# TBController_Teensy_3_2.net
KiCad netlist of a schematic drawn in EAGLE
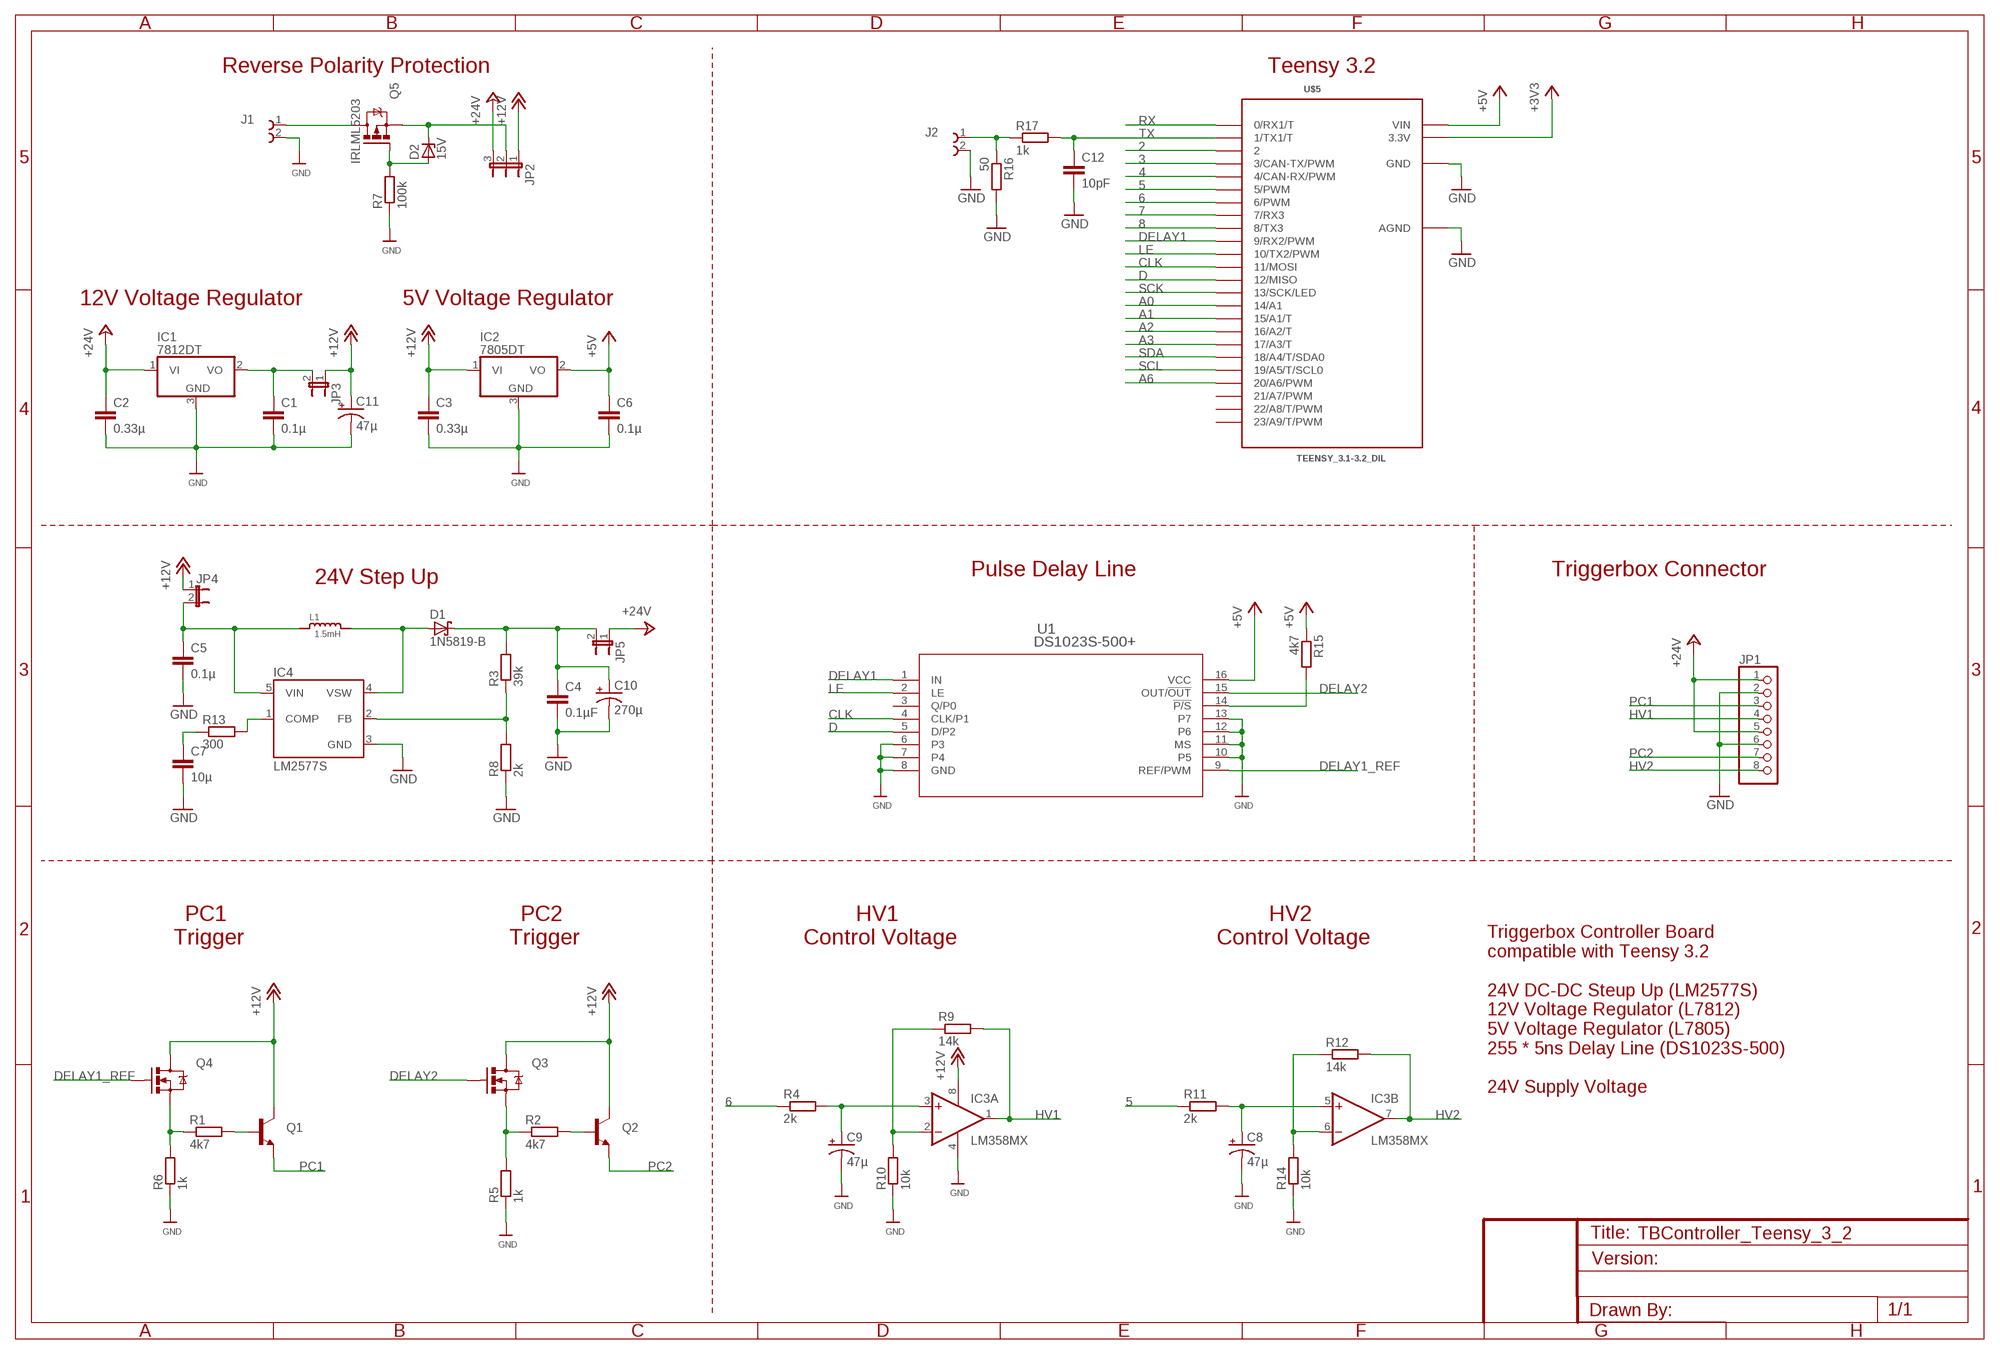
[diagram p0: schematic, sheet 1]

(export (version "E")
  (design (tool "Eeschema 10.0.6"))
  (components
    (comp (ref "C1")
      (value "0.1µ")
      (footprint "eagle-import:C0805K")
      (libsource (lib "eagle-import") (part "C-EUC0805K"))
    )
    (comp (ref "C2")
      (value "0.33µ")
      (footprint "eagle-import:C0805K")
      (libsource (lib "eagle-import") (part "C-EUC0805K"))
    )
    (comp (ref "C3")
      (value "0.33µ")
      (footprint "eagle-import:C0805K")
      (libsource (lib "eagle-import") (part "C-EUC0805K"))
    )
    (comp (ref "C4")
      (value "0.1µF")
      (footprint "eagle-import:C0805K")
      (libsource (lib "eagle-import") (part "C-EUC0805K"))
    )
    (comp (ref "C5")
      (value "0.1µ")
      (footprint "eagle-import:C0805K")
      (libsource (lib "eagle-import") (part "C-EUC0805K"))
    )
    (comp (ref "C6")
      (value "0.1µ")
      (footprint "eagle-import:C0805K")
      (libsource (lib "eagle-import") (part "C-EUC0805K"))
    )
    (comp (ref "C7")
      (value "10µ")
      (footprint "eagle-import:C0805K")
      (libsource (lib "eagle-import") (part "C-EUC0805K"))
    )
    (comp (ref "C8")
      (value "47µ")
      (footprint "eagle-import:CPOL-RADIAL-100UF-25V")
      (libsource (lib "eagle-import") (part "CAP_POLPTH1"))
    )
    (comp (ref "C9")
      (value "47µ")
      (footprint "eagle-import:CPOL-RADIAL-100UF-25V")
      (libsource (lib "eagle-import") (part "CAP_POLPTH1"))
    )
    (comp (ref "C10")
      (value "270µ")
      (footprint "eagle-import:CPOL-RADIAL-100UF-25V")
      (libsource (lib "eagle-import") (part "CAP_POLPTH1"))
    )
    (comp (ref "C11")
      (value "47µ")
      (footprint "eagle-import:CPOL-RADIAL-100UF-25V")
      (libsource (lib "eagle-import") (part "CAP_POLPTH1"))
    )
    (comp (ref "C12")
      (value "10pF")
      (footprint "eagle-import:C0805K")
      (libsource (lib "eagle-import") (part "C-EUC0805K"))
    )
    (comp (ref "D1")
      (value "1N5819-B")
      (footprint "eagle-import:DO41-7.6")
      (libsource (lib "eagle-import") (part "1N5819-B"))
    )
    (comp (ref "D2")
      (value "15V")
      (footprint "eagle-import:SOT23")
      (libsource (lib "eagle-import") (part "ZENER-DIODESOT23"))
    )
    (comp (ref "IC1")
      (value "7812DT")
      (footprint "eagle-import:TO252")
      (libsource (lib "eagle-import") (part "78DT12"))
    )
    (comp (ref "IC2")
      (value "7805DT")
      (footprint "eagle-import:TO252")
      (libsource (lib "eagle-import") (part "78DT05"))
    )
    (comp (ref "IC3")
      (value "LM358MX")
      (footprint "eagle-import:SO08")
      (libsource (lib "eagle-import") (part "LM358MX"))
    )
    (comp (ref "IC4")
      (value "LM2577S")
      (footprint "eagle-import:TO263-5")
      (libsource (lib "eagle-import") (part "LM2577S"))
    )
    (comp (ref "J1")
      (value "691103110002")
      (footprint "eagle-import:691103110002")
      (libsource (lib "eagle-import") (part "691103110002"))
    )
    (comp (ref "J2")
      (value "691103110002")
      (footprint "eagle-import:691103110002")
      (libsource (lib "eagle-import") (part "691103110002"))
    )
    (comp (ref "JP1")
      (value "PINHD-1X8")
      (footprint "eagle-import:1X08")
      (libsource (lib "eagle-import") (part "PINHD-1X8"))
    )
    (comp (ref "JP2")
      (value "JP2E")
      (footprint "eagle-import:JP2")
      (libsource (lib "eagle-import") (part "JP2E"))
    )
    (comp (ref "JP3")
      (value "JUMPER-2PTH_LOCK")
      (footprint "eagle-import:1X02_LOCK")
      (libsource (lib "eagle-import") (part "JUMPER-2PTH_LOCK"))
    )
    (comp (ref "JP4")
      (value "JUMPER-2PTH_LOCK")
      (footprint "eagle-import:1X02_LOCK")
      (libsource (lib "eagle-import") (part "JUMPER-2PTH_LOCK"))
    )
    (comp (ref "JP5")
      (value "JUMPER-2PTH_LOCK")
      (footprint "eagle-import:1X02_LOCK")
      (libsource (lib "eagle-import") (part "JUMPER-2PTH_LOCK"))
    )
    (comp (ref "L1")
      (value "1.5mH")
      (footprint "eagle-import:WUERTH_WE_PD")
      (libsource (lib "eagle-import") (part "SPULE"))
    )
    (comp (ref "Q1")
      (value "TRANSISTOR_NPNSOT23")
      (footprint "eagle-import:SOT23")
      (libsource (lib "eagle-import") (part "TRANSISTOR_NPNSOT23"))
    )
    (comp (ref "Q2")
      (value "TRANSISTOR_NPNSOT23")
      (footprint "eagle-import:SOT23")
      (libsource (lib "eagle-import") (part "TRANSISTOR_NPNSOT23"))
    )
    (comp (ref "Q3")
      (value "MOSFET-NCHANNELSMD")
      (footprint "eagle-import:SOT23-3")
      (libsource (lib "eagle-import") (part "MOSFET-NCHANNELSMD"))
    )
    (comp (ref "Q4")
      (value "MOSFET-NCHANNELSMD")
      (footprint "eagle-import:SOT23-3")
      (libsource (lib "eagle-import") (part "MOSFET-NCHANNELSMD"))
    )
    (comp (ref "Q5")
      (value "IRLML5203")
      (footprint "eagle-import:MICRO3")
      (libsource (lib "eagle-import") (part "IRLML5203"))
    )
    (comp (ref "R1")
      (value "4k7")
      (footprint "eagle-import:R0805")
      (libsource (lib "eagle-import") (part "R-EU_R0805"))
    )
    (comp (ref "R2")
      (value "4k7")
      (footprint "eagle-import:R0805")
      (libsource (lib "eagle-import") (part "R-EU_R0805"))
    )
    (comp (ref "R3")
      (value "39k")
      (footprint "eagle-import:R0805")
      (libsource (lib "eagle-import") (part "R-EU_R0805"))
    )
    (comp (ref "R4")
      (value "2k")
      (footprint "eagle-import:R0805")
      (libsource (lib "eagle-import") (part "R-EU_R0805"))
    )
    (comp (ref "R5")
      (value "1k")
      (footprint "eagle-import:R0805")
      (libsource (lib "eagle-import") (part "R-EU_R0805"))
    )
    (comp (ref "R6")
      (value "1k")
      (footprint "eagle-import:R0805")
      (libsource (lib "eagle-import") (part "R-EU_R0805"))
    )
    (comp (ref "R7")
      (value "100k")
      (footprint "eagle-import:R0805")
      (libsource (lib "eagle-import") (part "R-EU_R0805"))
    )
    (comp (ref "R8")
      (value "2k")
      (footprint "eagle-import:R0805")
      (libsource (lib "eagle-import") (part "R-EU_R0805"))
    )
    (comp (ref "R9")
      (value "14k")
      (footprint "eagle-import:R0805")
      (libsource (lib "eagle-import") (part "R-EU_R0805"))
    )
    (comp (ref "R10")
      (value "10k")
      (footprint "eagle-import:R0805")
      (libsource (lib "eagle-import") (part "R-EU_R0805"))
    )
    (comp (ref "R11")
      (value "2k")
      (footprint "eagle-import:R0805")
      (libsource (lib "eagle-import") (part "R-EU_R0805"))
    )
    (comp (ref "R12")
      (value "14k")
      (footprint "eagle-import:R0805")
      (libsource (lib "eagle-import") (part "R-EU_R0805"))
    )
    (comp (ref "R13")
      (value "300")
      (footprint "eagle-import:R0805")
      (libsource (lib "eagle-import") (part "R-EU_R0805"))
    )
    (comp (ref "R14")
      (value "10k")
      (footprint "eagle-import:R0805")
      (libsource (lib "eagle-import") (part "R-EU_R0805"))
    )
    (comp (ref "R15")
      (value "4k7")
      (footprint "eagle-import:R0805")
      (libsource (lib "eagle-import") (part "R-EU_R0805"))
    )
    (comp (ref "R16")
      (value "50")
      (footprint "eagle-import:R0805")
      (libsource (lib "eagle-import") (part "R-EU_R0805"))
    )
    (comp (ref "R17")
      (value "1k")
      (footprint "eagle-import:R0805")
      (libsource (lib "eagle-import") (part "R-EU_R0805"))
    )
    (comp (ref "U$5")
      (value "TEENSY_3.1-3.2_DIL")
      (footprint "eagle-import:TEENSY_3.0-3.2&LC_DIL")
      (libsource (lib "eagle-import") (part "TEENSY_3.1-3.2_DIL"))
    )
    (comp (ref "U1")
      (value "DS1023S-500+")
      (footprint "eagle-import:21-0042B_16")
      (fields (field (name "MANUFACTURER_PART_NUMBER") "DS1023S500+"))
      (libsource (lib "eagle-import") (part "DS1023S-500+"))
    )
  )
  (nets
    (net (code "1") (name "+3V3") (class "Default")
      (node (ref "U$5") (pin "3.3V") (pinfunction "3.3V_3.3V") (pintype "power_in"))
    )
    (net (code "2") (name "+5V") (class "Default")
      (node (ref "C6") (pin "1") (pinfunction "1_1") (pintype "passive"))
      (node (ref "IC2") (pin "2") (pinfunction "VO_2") (pintype "passive"))
      (node (ref "R15") (pin "1") (pinfunction "1_1") (pintype "passive"))
      (node (ref "U$5") (pin "VIN") (pinfunction "VIN_VIN") (pintype "power_in"))
      (node (ref "U1") (pin "16") (pinfunction "VCC_16") (pintype "power_in"))
    )
    (net (code "3") (name "+12V") (class "Default")
      (node (ref "C11") (pin "1") (pinfunction "+_1") (pintype "passive"))
      (node (ref "C3") (pin "1") (pinfunction "1_1") (pintype "passive"))
      (node (ref "IC2") (pin "1") (pinfunction "VI_1") (pintype "input"))
      (node (ref "IC3") (pin "8") (pinfunction "V+_8") (pintype "power_in"))
      (node (ref "JP2") (pin "1") (pinfunction "1_1") (pintype "passive"))
      (node (ref "JP3") (pin "1") (pinfunction "1_1") (pintype "passive"))
      (node (ref "JP4") (pin "1") (pinfunction "1_1") (pintype "passive"))
      (node (ref "Q1") (pin "3") (pinfunction "C_3") (pintype "passive"))
      (node (ref "Q2") (pin "3") (pinfunction "C_3") (pintype "passive"))
      (node (ref "Q3") (pin "3") (pinfunction "D_3") (pintype "passive"))
      (node (ref "Q4") (pin "3") (pinfunction "D_3") (pintype "passive"))
    )
    (net (code "4") (name "+24V") (class "Default")
      (node (ref "C2") (pin "1") (pinfunction "1_1") (pintype "passive"))
      (node (ref "IC1") (pin "1") (pinfunction "VI_1") (pintype "input"))
      (node (ref "JP1") (pin "1") (pinfunction "1_1") (pintype "passive"))
      (node (ref "JP1") (pin "5") (pinfunction "5_5") (pintype "passive"))
      (node (ref "JP2") (pin "3") (pinfunction "3_3") (pintype "passive"))
      (node (ref "JP5") (pin "1") (pinfunction "1_1") (pintype "passive"))
    )
    (net (code "5") (name "/2") (class "Default")
      (node (ref "U$5") (pin "2") (pinfunction "2_2") (pintype "bidirectional"))
    )
    (net (code "6") (name "/3") (class "Default")
      (node (ref "U$5") (pin "3") (pinfunction "3/CAN-TX/PWM_3") (pintype "bidirectional"))
    )
    (net (code "7") (name "/4") (class "Default")
      (node (ref "U$5") (pin "4") (pinfunction "4/CAN-RX/PWM_4") (pintype "bidirectional"))
    )
    (net (code "8") (name "/5") (class "Default")
      (node (ref "R11") (pin "1") (pinfunction "1_1") (pintype "passive"))
      (node (ref "U$5") (pin "5") (pinfunction "5/PWM_5") (pintype "bidirectional"))
    )
    (net (code "9") (name "/6") (class "Default")
      (node (ref "R4") (pin "1") (pinfunction "1_1") (pintype "passive"))
      (node (ref "U$5") (pin "6") (pinfunction "6/PWM_6") (pintype "bidirectional"))
    )
    (net (code "10") (name "/7") (class "Default")
      (node (ref "U$5") (pin "7") (pinfunction "7/RX3_7") (pintype "bidirectional"))
    )
    (net (code "11") (name "/8") (class "Default")
      (node (ref "U$5") (pin "8") (pinfunction "8/TX3_8") (pintype "bidirectional"))
    )
    (net (code "12") (name "/A0") (class "Default")
      (node (ref "U$5") (pin "14/A0") (pinfunction "14/A1_14/A0") (pintype "bidirectional"))
    )
    (net (code "13") (name "/A1") (class "Default")
      (node (ref "U$5") (pin "15/A1") (pinfunction "15/A1/T_15/A1") (pintype "bidirectional"))
    )
    (net (code "14") (name "/A2") (class "Default")
      (node (ref "U$5") (pin "16/A2") (pinfunction "16/A2/T_16/A2") (pintype "bidirectional"))
    )
    (net (code "15") (name "/A3") (class "Default")
      (node (ref "U$5") (pin "17/A3") (pinfunction "17/A3/T_17/A3") (pintype "bidirectional"))
    )
    (net (code "16") (name "/A6") (class "Default")
      (node (ref "U$5") (pin "20/A6") (pinfunction "20/A6/PWM_20/A6") (pintype "bidirectional"))
    )
    (net (code "17") (name "/CLK") (class "Default")
      (node (ref "U$5") (pin "11") (pinfunction "11/MOSI_11") (pintype "bidirectional"))
      (node (ref "U1") (pin "4") (pinfunction "CLK/P1_4") (pintype "passive"))
    )
    (net (code "18") (name "/D") (class "Default")
      (node (ref "U$5") (pin "12") (pinfunction "12/MISO_12") (pintype "bidirectional"))
      (node (ref "U1") (pin "5") (pinfunction "D/P2_5") (pintype "passive"))
    )
    (net (code "19") (name "/DELAY1") (class "Default")
      (node (ref "U$5") (pin "9") (pinfunction "9/RX2/PWM_9") (pintype "bidirectional"))
      (node (ref "U1") (pin "1") (pinfunction "IN_1") (pintype "input"))
    )
    (net (code "20") (name "/DELAY1_REF") (class "Default")
      (node (ref "Q4") (pin "1") (pinfunction "G_1") (pintype "passive"))
      (node (ref "U1") (pin "9") (pinfunction "REF/PWM_9") (pintype "passive"))
    )
    (net (code "21") (name "/DELAY2") (class "Default")
      (node (ref "Q3") (pin "1") (pinfunction "G_1") (pintype "passive"))
      (node (ref "U1") (pin "15") (pinfunction "OUT/~{OUT}_15") (pintype "passive"))
    )
    (net (code "22") (name "/HV1") (class "Default")
      (node (ref "IC3") (pin "1") (pinfunction "OUT_1") (pintype "output"))
      (node (ref "JP1") (pin "4") (pinfunction "4_4") (pintype "passive"))
      (node (ref "R9") (pin "2") (pinfunction "2_2") (pintype "passive"))
    )
    (net (code "23") (name "/HV2") (class "Default")
      (node (ref "IC3") (pin "7") (pinfunction "OUT_7") (pintype "output"))
      (node (ref "JP1") (pin "8") (pinfunction "8_8") (pintype "passive"))
      (node (ref "R12") (pin "2") (pinfunction "2_2") (pintype "passive"))
    )
    (net (code "24") (name "/LE") (class "Default")
      (node (ref "U$5") (pin "10") (pinfunction "10/TX2/PWM_10") (pintype "bidirectional"))
      (node (ref "U1") (pin "2") (pinfunction "LE_2") (pintype "passive"))
    )
    (net (code "25") (name "/PC1") (class "Default")
      (node (ref "JP1") (pin "3") (pinfunction "3_3") (pintype "passive"))
      (node (ref "Q1") (pin "2") (pinfunction "E_2") (pintype "passive"))
    )
    (net (code "26") (name "/PC2") (class "Default")
      (node (ref "JP1") (pin "7") (pinfunction "7_7") (pintype "passive"))
      (node (ref "Q2") (pin "2") (pinfunction "E_2") (pintype "passive"))
    )
    (net (code "27") (name "/RX") (class "Default")
      (node (ref "U$5") (pin "0") (pinfunction "0/RX1/T_0") (pintype "bidirectional"))
    )
    (net (code "28") (name "/SCK") (class "Default")
      (node (ref "U$5") (pin "13") (pinfunction "13/SCK/LED_13") (pintype "bidirectional"))
    )
    (net (code "29") (name "/SCL") (class "Default")
      (node (ref "U$5") (pin "19/A5") (pinfunction "19/A5/T/SCL0_19/A5") (pintype "bidirectional"))
    )
    (net (code "30") (name "/SDA") (class "Default")
      (node (ref "U$5") (pin "18/A4") (pinfunction "18/A4/T/SDA0_18/A4") (pintype "bidirectional"))
    )
    (net (code "31") (name "/TX") (class "Default")
      (node (ref "J2") (pin "1") (pinfunction "1_1") (pintype "passive"))
      (node (ref "R16") (pin "1") (pinfunction "1_1") (pintype "passive"))
      (node (ref "R17") (pin "1") (pinfunction "1_1") (pintype "passive"))
    )
    (net (code "32") (name "GND") (class "Default")
      (node (ref "C1") (pin "2") (pinfunction "2_2") (pintype "passive"))
      (node (ref "C10") (pin "2") (pinfunction "-_2") (pintype "passive"))
      (node (ref "C11") (pin "2") (pinfunction "-_2") (pintype "passive"))
      (node (ref "C12") (pin "2") (pinfunction "2_2") (pintype "passive"))
      (node (ref "C2") (pin "2") (pinfunction "2_2") (pintype "passive"))
      (node (ref "C3") (pin "2") (pinfunction "2_2") (pintype "passive"))
      (node (ref "C4") (pin "2") (pinfunction "2_2") (pintype "passive"))
      (node (ref "C5") (pin "2") (pinfunction "2_2") (pintype "passive"))
      (node (ref "C6") (pin "2") (pinfunction "2_2") (pintype "passive"))
      (node (ref "C7") (pin "2") (pinfunction "2_2") (pintype "passive"))
      (node (ref "C8") (pin "2") (pinfunction "-_2") (pintype "passive"))
      (node (ref "C9") (pin "2") (pinfunction "-_2") (pintype "passive"))
      (node (ref "IC1") (pin "3") (pinfunction "GND_3") (pintype "passive"))
      (node (ref "IC2") (pin "3") (pinfunction "GND_3") (pintype "passive"))
      (node (ref "IC3") (pin "4") (pinfunction "V-_4") (pintype "power_in"))
      (node (ref "IC4") (pin "3") (pinfunction "GND_3") (pintype "power_in"))
      (node (ref "J1") (pin "2") (pinfunction "2_2") (pintype "passive"))
      (node (ref "J2") (pin "2") (pinfunction "2_2") (pintype "passive"))
      (node (ref "JP1") (pin "2") (pinfunction "2_2") (pintype "passive"))
      (node (ref "JP1") (pin "6") (pinfunction "6_6") (pintype "passive"))
      (node (ref "R10") (pin "1") (pinfunction "1_1") (pintype "passive"))
      (node (ref "R14") (pin "1") (pinfunction "1_1") (pintype "passive"))
      (node (ref "R16") (pin "2") (pinfunction "2_2") (pintype "passive"))
      (node (ref "R5") (pin "1") (pinfunction "1_1") (pintype "passive"))
      (node (ref "R6") (pin "1") (pinfunction "1_1") (pintype "passive"))
      (node (ref "R7") (pin "1") (pinfunction "1_1") (pintype "passive"))
      (node (ref "R8") (pin "1") (pinfunction "1_1") (pintype "passive"))
      (node (ref "U$5") (pin "AGND") (pinfunction "AGND_AGND") (pintype "power_in"))
      (node (ref "U$5") (pin "GND") (pinfunction "GND_GND") (pintype "power_in"))
      (node (ref "U1") (pin "10") (pinfunction "P5_10") (pintype "passive"))
      (node (ref "U1") (pin "11") (pinfunction "MS_11") (pintype "passive"))
      (node (ref "U1") (pin "12") (pinfunction "P6_12") (pintype "passive"))
      (node (ref "U1") (pin "13") (pinfunction "P7_13") (pintype "passive"))
      (node (ref "U1") (pin "6") (pinfunction "P3_6") (pintype "passive"))
      (node (ref "U1") (pin "7") (pinfunction "P4_7") (pintype "passive"))
      (node (ref "U1") (pin "8") (pinfunction "GND_8") (pintype "power_in"))
    )
    (net (code "33") (name "Net-(C7-Pad1)") (class "Default")
      (node (ref "C7") (pin "1") (pinfunction "1_1") (pintype "passive"))
      (node (ref "R13") (pin "1") (pinfunction "1_1") (pintype "passive"))
    )
    (net (code "34") (name "Net-(C8-+)") (class "Default")
      (node (ref "C8") (pin "1") (pinfunction "+_1") (pintype "passive"))
      (node (ref "IC3") (pin "5") (pinfunction "+IN_5") (pintype "input"))
      (node (ref "R11") (pin "2") (pinfunction "2_2") (pintype "passive"))
    )
    (net (code "35") (name "Net-(C9-+)") (class "Default")
      (node (ref "C9") (pin "1") (pinfunction "+_1") (pintype "passive"))
      (node (ref "IC3") (pin "3") (pinfunction "+IN_3") (pintype "input"))
      (node (ref "R4") (pin "2") (pinfunction "2_2") (pintype "passive"))
    )
    (net (code "36") (name "Net-(C10-+)") (class "Default")
      (node (ref "C10") (pin "1") (pinfunction "+_1") (pintype "passive"))
      (node (ref "C4") (pin "1") (pinfunction "1_1") (pintype "passive"))
      (node (ref "D1") (pin "C") (pinfunction "C_C") (pintype "passive"))
      (node (ref "JP5") (pin "2") (pinfunction "2_2") (pintype "passive"))
      (node (ref "R3") (pin "2") (pinfunction "2_2") (pintype "passive"))
    )
    (net (code "37") (name "Net-(D2-A)") (class "Default")
      (node (ref "D2") (pin "1") (pinfunction "A_1") (pintype "passive"))
      (node (ref "Q5") (pin "1") (pinfunction "G_1") (pintype "passive"))
      (node (ref "R7") (pin "2") (pinfunction "2_2") (pintype "passive"))
    )
    (net (code "38") (name "Net-(D2-C)") (class "Default")
      (node (ref "D2") (pin "3") (pinfunction "C_3") (pintype "passive"))
      (node (ref "JP2") (pin "2") (pinfunction "2_2") (pintype "passive"))
      (node (ref "Q5") (pin "2") (pinfunction "S_2") (pintype "passive"))
    )
    (net (code "39") (name "Net-(IC1-VO)") (class "Default")
      (node (ref "C1") (pin "1") (pinfunction "1_1") (pintype "passive"))
      (node (ref "IC1") (pin "2") (pinfunction "VO_2") (pintype "passive"))
      (node (ref "JP3") (pin "2") (pinfunction "2_2") (pintype "passive"))
    )
    (net (code "40") (name "Net-(IC3A--IN)") (class "Default")
      (node (ref "IC3") (pin "2") (pinfunction "-IN_2") (pintype "input"))
      (node (ref "R10") (pin "2") (pinfunction "2_2") (pintype "passive"))
      (node (ref "R9") (pin "1") (pinfunction "1_1") (pintype "passive"))
    )
    (net (code "41") (name "Net-(IC3B--IN)") (class "Default")
      (node (ref "IC3") (pin "6") (pinfunction "-IN_6") (pintype "input"))
      (node (ref "R12") (pin "1") (pinfunction "1_1") (pintype "passive"))
      (node (ref "R14") (pin "2") (pinfunction "2_2") (pintype "passive"))
    )
    (net (code "42") (name "Net-(IC4-COMP)") (class "Default")
      (node (ref "IC4") (pin "1") (pinfunction "COMP_1") (pintype "passive"))
      (node (ref "R13") (pin "2") (pinfunction "2_2") (pintype "passive"))
    )
    (net (code "43") (name "Net-(IC4-FB)") (class "Default")
      (node (ref "IC4") (pin "2") (pinfunction "FB_2") (pintype "input"))
      (node (ref "R3") (pin "1") (pinfunction "1_1") (pintype "passive"))
      (node (ref "R8") (pin "2") (pinfunction "2_2") (pintype "passive"))
    )
    (net (code "44") (name "Net-(IC4-VIN)") (class "Default")
      (node (ref "C5") (pin "1") (pinfunction "1_1") (pintype "passive"))
      (node (ref "IC4") (pin "5") (pinfunction "VIN_5") (pintype "power_in"))
      (node (ref "JP4") (pin "2") (pinfunction "2_2") (pintype "passive"))
      (node (ref "L1") (pin "1") (pinfunction "P$1_1") (pintype "bidirectional"))
    )
    (net (code "45") (name "Net-(IC4-VSW)") (class "Default")
      (node (ref "D1") (pin "A") (pinfunction "A_A") (pintype "passive"))
      (node (ref "IC4") (pin "4") (pinfunction "VSW_4") (pintype "bidirectional"))
      (node (ref "L1") (pin "2") (pinfunction "P$2_2") (pintype "bidirectional"))
    )
    (net (code "46") (name "Net-(Q1-B)") (class "Default")
      (node (ref "Q1") (pin "1") (pinfunction "B_1") (pintype "passive"))
      (node (ref "R1") (pin "2") (pinfunction "2_2") (pintype "passive"))
    )
    (net (code "47") (name "Net-(Q2-B)") (class "Default")
      (node (ref "Q2") (pin "1") (pinfunction "B_1") (pintype "passive"))
      (node (ref "R2") (pin "2") (pinfunction "2_2") (pintype "passive"))
    )
    (net (code "48") (name "Net-(Q3-S)") (class "Default")
      (node (ref "Q3") (pin "2") (pinfunction "S_2") (pintype "passive"))
      (node (ref "R2") (pin "1") (pinfunction "1_1") (pintype "passive"))
      (node (ref "R5") (pin "2") (pinfunction "2_2") (pintype "passive"))
    )
    (net (code "49") (name "Net-(Q4-S)") (class "Default")
      (node (ref "Q4") (pin "2") (pinfunction "S_2") (pintype "passive"))
      (node (ref "R1") (pin "1") (pinfunction "1_1") (pintype "passive"))
      (node (ref "R6") (pin "2") (pinfunction "2_2") (pintype "passive"))
    )
    (net (code "50") (name "Net-(Q5-D)") (class "Default")
      (node (ref "J1") (pin "1") (pinfunction "1_1") (pintype "passive"))
      (node (ref "Q5") (pin "3") (pinfunction "D_3") (pintype "passive"))
    )
    (net (code "51") (name "Net-(U$5-1{slash}TX1{slash}T)") (class "Default")
      (node (ref "C12") (pin "1") (pinfunction "1_1") (pintype "passive"))
      (node (ref "R17") (pin "2") (pinfunction "2_2") (pintype "passive"))
      (node (ref "U$5") (pin "1") (pinfunction "1/TX1/T_1") (pintype "bidirectional"))
    )
    (net (code "52") (name "Net-(U1-~{P{slash}S})") (class "Default")
      (node (ref "R15") (pin "2") (pinfunction "2_2") (pintype "passive"))
      (node (ref "U1") (pin "14") (pinfunction "~{P/S}_14") (pintype "passive"))
    )
    (net (code "53") (name "unconnected-(U$5-21{slash}A7{slash}PWM-Pad21{slash}A7)") (class "Default")
      (node (ref "U$5") (pin "21/A7") (pinfunction "21/A7/PWM_21/A7") (pintype "bidirectional"))
    )
    (net (code "54") (name "unconnected-(U$5-22{slash}A8{slash}T{slash}PWM-Pad22{slash}A8)") (class "Default")
      (node (ref "U$5") (pin "22/A8") (pinfunction "22/A8/T/PWM_22/A8") (pintype "bidirectional"))
    )
    (net (code "55") (name "unconnected-(U$5-23{slash}A9{slash}T{slash}PWM-Pad23{slash}A9)") (class "Default")
      (node (ref "U$5") (pin "23/A9") (pinfunction "23/A9/T/PWM_23/A9") (pintype "bidirectional"))
    )
    (net (code "56") (name "unconnected-(U1-Q{slash}P0-Pad3)") (class "Default")
      (node (ref "U1") (pin "3") (pinfunction "Q/P0_3") (pintype "passive"))
    )
  )
)
